# MCU.net
KiCad netlist of a schematic drawn in Altium Designer
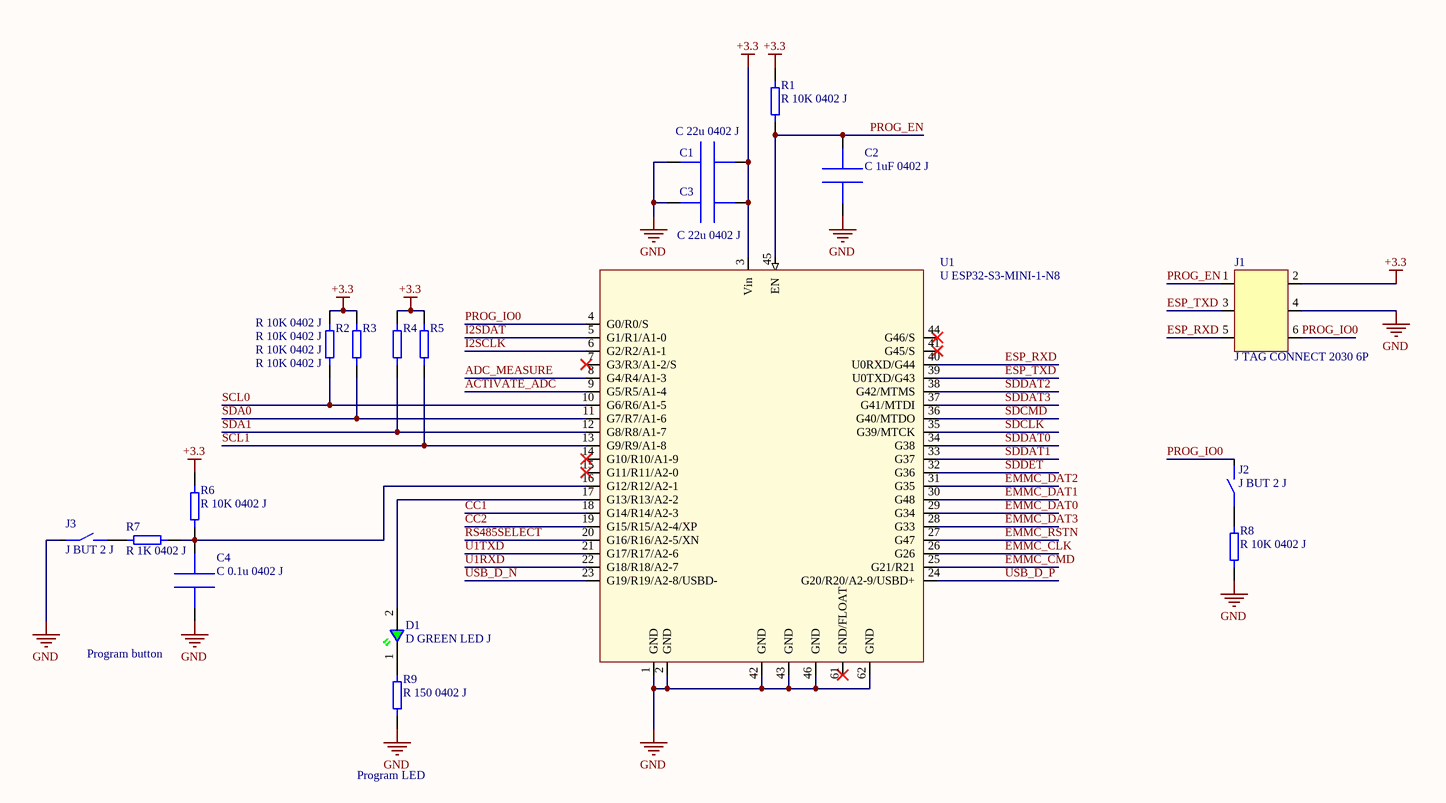
[diagram p0: MCU.SchDoc]

(export (version "E")
  (design (tool "Eeschema 10.0.6"))
  (components
    (comp (ref "C1")
      (value "C 22u 0402 J")
      (footprint "C0402")
      (description "Multi-Layer Ceramic Capacitor 22uF 2.5VDC X6S 20% 0402 Paper T/R GRM155C80E226ME11D")
      (fields
        (field (name "MANUFACTURER") "Murata")
        (field (name "MANUFACTURER PART NUMBER") "GRM155C80E226ME11D")
      )
      (libsource (lib "Schlib1") (part "C 22u 0402 J"))
    )
    (comp (ref "C2")
      (value "C 1uF 0402 J")
      (footprint "C0402")
      (description "Ceramic capacitor SMD 0402 - 1000nF, 10V, +-10%, X5R CL05A105KP5NNNC")
      (fields
        (field (name "MANUFACTURER") "Samsung")
        (field (name "MANUFACTURER PART NUMBER") "CL05A105KP5NNNC")
      )
      (libsource (lib "Schlib1") (part "C 1uF 0402 J"))
    )
    (comp (ref "C3")
      (value "C 22u 0402 J")
      (footprint "C0402")
      (description "Multi-Layer Ceramic Capacitor 22uF 2.5VDC X6S 20% 0402 Paper T/R GRM155C80E226ME11D")
      (fields
        (field (name "MANUFACTURER") "Murata")
        (field (name "MANUFACTURER PART NUMBER") "GRM155C80E226ME11D")
      )
      (libsource (lib "Schlib1") (part "C 22u 0402 J"))
    )
    (comp (ref "C4")
      (value "C 0.1u 0402 J")
      (footprint "C0402")
      (description "Cap Ceramic 0.1uF 50V X7R 10% Pad SMD 0402 125C Low ESR Automotive CL05B104KB54PNC")
      (fields
        (field (name "MANUFACTURER") "Samsung")
        (field (name "MANUFACTURER PART NUMBER") "CL05B104KB54PNC")
      )
      (libsource (lib "Schlib1") (part "C 0.1u 0402 J"))
    )
    (comp (ref "D1")
      (value "D GREEN LED J")
      (footprint "NCD0402C1")
      (description "Green/Yellow-Green 0402 Light Emitting Diodes (LED) ROHS NCD0402C1")
      (fields
        (field (name "MANUFACTURER") "Foshan NationStar Optoelectronics")
        (field (name "MANUFACTURER PART NUMBER") "NCD0402C1")
      )
      (libsource (lib "Schlib1") (part "D GREEN LED J"))
    )
    (comp (ref "J1")
      (value "J TAG CONNECT 2030 6P")
      (footprint "TAG-CONNECT-6")
      (description "Direct programming with TAG CONNECT 2030")
      (libsource (lib "Schlib1") (part "J TAG CONNECT 2030 6P"))
    )
    (comp (ref "J2")
      (value "J BUT 2 J")
      (footprint "ALPSALPINE BUTTON")
      (description "Switch Tactile N.O. SPST Round Button Gull Wing 0.05A 12VDC 1.57N SMD T/R SKRKAEE020")
      (fields
        (field (name "MANUFACTURER") "Alps Electric")
        (field (name "MANUFACTURER PART NUMBER") "SKRKAEE020")
      )
      (libsource (lib "Schlib1") (part "J BUT 2 J"))
    )
    (comp (ref "J3")
      (value "J BUT 2 J")
      (footprint "ALPSALPINE BUTTON")
      (description "Switch Tactile N.O. SPST Round Button Gull Wing 0.05A 12VDC 1.57N SMD T/R SKRKAEE020")
      (fields
        (field (name "MANUFACTURER") "Alps Electric")
        (field (name "MANUFACTURER PART NUMBER") "SKRKAEE020")
      )
      (libsource (lib "Schlib1") (part "J BUT 2 J"))
    )
    (comp (ref "R1")
      (value "R 10K 0402 J")
      (footprint "R0402")
      (description "Res Thick Film 0402 10K Ohm 1% 0.063W(1/16W) ±100ppm/C Pad SMD Automotive T/R AC0402FR-0710KL")
      (fields
        (field (name "MANUFACTURER") "Yageo")
        (field (name "MANUFACTURER PART NUMBER") "AC0402FR-0710KL")
      )
      (libsource (lib "Schlib1") (part "R 10K 0402 J"))
    )
    (comp (ref "R2")
      (value "R 10K 0402 J")
      (footprint "R0402")
      (description "Res Thick Film 0402 10K Ohm 1% 0.063W(1/16W) ±100ppm/C Pad SMD Automotive T/R AC0402FR-0710KL")
      (fields
        (field (name "MANUFACTURER") "Yageo")
        (field (name "MANUFACTURER PART NUMBER") "AC0402FR-0710KL")
      )
      (libsource (lib "Schlib1") (part "R 10K 0402 J"))
    )
    (comp (ref "R3")
      (value "R 10K 0402 J")
      (footprint "R0402")
      (description "Res Thick Film 0402 10K Ohm 1% 0.063W(1/16W) ±100ppm/C Pad SMD Automotive T/R AC0402FR-0710KL")
      (fields
        (field (name "MANUFACTURER") "Yageo")
        (field (name "MANUFACTURER PART NUMBER") "AC0402FR-0710KL")
      )
      (libsource (lib "Schlib1") (part "R 10K 0402 J"))
    )
    (comp (ref "R4")
      (value "R 10K 0402 J")
      (footprint "R0402")
      (description "Res Thick Film 0402 10K Ohm 1% 0.063W(1/16W) ±100ppm/C Pad SMD Automotive T/R AC0402FR-0710KL")
      (fields
        (field (name "MANUFACTURER") "Yageo")
        (field (name "MANUFACTURER PART NUMBER") "AC0402FR-0710KL")
      )
      (libsource (lib "Schlib1") (part "R 10K 0402 J"))
    )
    (comp (ref "R5")
      (value "R 10K 0402 J")
      (footprint "R0402")
      (description "Res Thick Film 0402 10K Ohm 1% 0.063W(1/16W) ±100ppm/C Pad SMD Automotive T/R AC0402FR-0710KL")
      (fields
        (field (name "MANUFACTURER") "Yageo")
        (field (name "MANUFACTURER PART NUMBER") "AC0402FR-0710KL")
      )
      (libsource (lib "Schlib1") (part "R 10K 0402 J"))
    )
    (comp (ref "R6")
      (value "R 10K 0402 J")
      (footprint "R0402")
      (description "Res Thick Film 0402 10K Ohm 1% 0.063W(1/16W) ±100ppm/C Pad SMD Automotive T/R AC0402FR-0710KL")
      (fields
        (field (name "MANUFACTURER") "Yageo")
        (field (name "MANUFACTURER PART NUMBER") "AC0402FR-0710KL")
      )
      (libsource (lib "Schlib1") (part "R 10K 0402 J"))
    )
    (comp (ref "R7")
      (value "R 1K 0402 J")
      (footprint "R0402")
      (description "Res Thick Film 0402 1K Ohm 1% 0.063W(1/16W) ±100ppm/C Pad SMD Automotive T/R")
      (fields
        (field (name "MANUFACTURER") "Yageo")
        (field (name "MANUFACTURER PART NUMBER") "AC0402FR-071KL")
      )
      (libsource (lib "Schlib1") (part "R 1K 0402 J"))
    )
    (comp (ref "R8")
      (value "R 10K 0402 J")
      (footprint "R0402")
      (description "Res Thick Film 0402 10K Ohm 1% 0.063W(1/16W) ±100ppm/C Pad SMD Automotive T/R AC0402FR-0710KL")
      (fields
        (field (name "MANUFACTURER") "Yageo")
        (field (name "MANUFACTURER PART NUMBER") "AC0402FR-0710KL")
      )
      (libsource (lib "Schlib1") (part "R 10K 0402 J"))
    )
    (comp (ref "R9")
      (value "R 150 0402 J")
      (footprint "R0402")
      (fields
        (field (name "MANUFACTURER") "Yageo")
        (field (name "MANUFACTURER PART NUMBER") "RC0402FR-07150RL")
        (field (name "TOLERANCE") "1%")
      )
      (libsource (lib "Schlib1") (part "R 150 0402 J"))
    )
    (comp (ref "U1")
      (value "U ESP32-S3-MINI-1-N8")
      (footprint "ESP-S3-MINI")
      (description "SMD Module, ESP32-S3FN8, 8 mb Sp ESP32-S3-MINI-1-N8")
      (fields
        (field (name "MANUFACTURER") "Espressif Systems")
        (field (name "MANUFACTURER PART NUMBER") "ESP32-S3-MINI-1-N8")
      )
      (libsource (lib "Schlib1") (part "U ESP32-S3-MINI-1-N8"))
    )
  )
  (nets
    (net (code "1") (name "+3.3") (class "Default")
      (node (ref "C1") (pin "1") (pinfunction "1_1") (pintype "passive"))
      (node (ref "C3") (pin "1") (pinfunction "1_1") (pintype "passive"))
      (node (ref "J1") (pin "2") (pintype "passive"))
      (node (ref "R1") (pin "2") (pinfunction "2_2") (pintype "passive"))
      (node (ref "R2") (pin "2") (pinfunction "2_2") (pintype "passive"))
      (node (ref "R3") (pin "2") (pinfunction "2_2") (pintype "passive"))
      (node (ref "R4") (pin "2") (pinfunction "2_2") (pintype "passive"))
      (node (ref "R5") (pin "2") (pinfunction "2_2") (pintype "passive"))
      (node (ref "R6") (pin "2") (pinfunction "2_2") (pintype "passive"))
      (node (ref "U1") (pin "3") (pinfunction "Vin_3") (pintype "power_in"))
    )
    (net (code "2") (name "/ACTIVATE_ADC") (class "Default")
      (node (ref "U1") (pin "9") (pinfunction "G5/R5/A1-4_9") (pintype "bidirectional"))
    )
    (net (code "3") (name "/ADC_MEASURE") (class "Default")
      (node (ref "U1") (pin "8") (pinfunction "G4/R4/A1-3_8") (pintype "bidirectional"))
    )
    (net (code "4") (name "/CC1") (class "Default")
      (node (ref "U1") (pin "18") (pinfunction "G14/R14/A2-3_18") (pintype "bidirectional"))
    )
    (net (code "5") (name "/CC2") (class "Default")
      (node (ref "U1") (pin "19") (pinfunction "G15/R15/A2-4/XP_19") (pintype "bidirectional"))
    )
    (net (code "6") (name "/EMMC_CLK") (class "Default")
      (node (ref "U1") (pin "26") (pinfunction "G26_26") (pintype "bidirectional"))
    )
    (net (code "7") (name "/EMMC_CMD") (class "Default")
      (node (ref "U1") (pin "25") (pinfunction "G21/R21_25") (pintype "bidirectional"))
    )
    (net (code "8") (name "/EMMC_DAT0") (class "Default")
      (node (ref "U1") (pin "29") (pinfunction "G34_29") (pintype "bidirectional"))
    )
    (net (code "9") (name "/EMMC_DAT1") (class "Default")
      (node (ref "U1") (pin "30") (pinfunction "G48_30") (pintype "bidirectional"))
    )
    (net (code "10") (name "/EMMC_DAT2") (class "Default")
      (node (ref "U1") (pin "31") (pinfunction "G35_31") (pintype "bidirectional"))
    )
    (net (code "11") (name "/EMMC_DAT3") (class "Default")
      (node (ref "U1") (pin "28") (pinfunction "G33_28") (pintype "bidirectional"))
    )
    (net (code "12") (name "/EMMC_RSTN") (class "Default")
      (node (ref "U1") (pin "27") (pinfunction "G47_27") (pintype "bidirectional"))
    )
    (net (code "13") (name "/ESP_RXD") (class "Default")
      (node (ref "J1") (pin "5") (pintype "passive"))
      (node (ref "U1") (pin "40") (pinfunction "U0RXD/G44_40") (pintype "bidirectional"))
    )
    (net (code "14") (name "/ESP_TXD") (class "Default")
      (node (ref "J1") (pin "3") (pintype "passive"))
      (node (ref "U1") (pin "39") (pinfunction "U0TXD/G43_39") (pintype "bidirectional"))
    )
    (net (code "15") (name "/I2SCLK") (class "Default")
      (node (ref "U1") (pin "6") (pinfunction "G2/R2/A1-1_6") (pintype "bidirectional"))
    )
    (net (code "16") (name "/I2SDAT") (class "Default")
      (node (ref "U1") (pin "5") (pinfunction "G1/R1/A1-0_5") (pintype "bidirectional"))
    )
    (net (code "17") (name "/PROG_EN") (class "Default")
      (node (ref "C2") (pin "2") (pinfunction "2_2") (pintype "passive"))
      (node (ref "J1") (pin "1") (pintype "passive"))
      (node (ref "R1") (pin "1") (pinfunction "1_1") (pintype "passive"))
      (node (ref "U1") (pin "45") (pinfunction "EN_45") (pintype "input"))
    )
    (net (code "18") (name "/PROG_IO0") (class "Default")
      (node (ref "J1") (pin "6") (pintype "passive"))
      (node (ref "J2") (pin "2") (pinfunction "2_2") (pintype "passive"))
      (node (ref "U1") (pin "4") (pinfunction "G0/R0/S_4") (pintype "bidirectional"))
    )
    (net (code "19") (name "/RS485SELECT") (class "Default")
      (node (ref "U1") (pin "20") (pinfunction "G16/R16/A2-5/XN_20") (pintype "bidirectional"))
    )
    (net (code "20") (name "/SCL0") (class "Default")
      (node (ref "R2") (pin "1") (pinfunction "1_1") (pintype "passive"))
      (node (ref "U1") (pin "10") (pinfunction "G6/R6/A1-5_10") (pintype "bidirectional"))
    )
    (net (code "21") (name "/SCL1") (class "Default")
      (node (ref "R5") (pin "1") (pinfunction "1_1") (pintype "passive"))
      (node (ref "U1") (pin "13") (pinfunction "G9/R9/A1-8_13") (pintype "bidirectional"))
    )
    (net (code "22") (name "/SDA1") (class "Default")
      (node (ref "R4") (pin "1") (pinfunction "1_1") (pintype "passive"))
      (node (ref "U1") (pin "12") (pinfunction "G8/R8/A1-7_12") (pintype "bidirectional"))
    )
    (net (code "23") (name "/SDA~{0}") (class "Default")
      (node (ref "R3") (pin "1") (pinfunction "1_1") (pintype "passive"))
      (node (ref "U1") (pin "11") (pinfunction "G7/R7/A1-6_11") (pintype "bidirectional"))
    )
    (net (code "24") (name "/SDCLK") (class "Default")
      (node (ref "U1") (pin "35") (pinfunction "G39/MTCK_35") (pintype "bidirectional"))
    )
    (net (code "25") (name "/SDCMD") (class "Default")
      (node (ref "U1") (pin "36") (pinfunction "G40/MTDO_36") (pintype "bidirectional"))
    )
    (net (code "26") (name "/SDDAT0") (class "Default")
      (node (ref "U1") (pin "34") (pinfunction "G38_34") (pintype "bidirectional"))
    )
    (net (code "27") (name "/SDDAT1") (class "Default")
      (node (ref "U1") (pin "33") (pinfunction "G37_33") (pintype "bidirectional"))
    )
    (net (code "28") (name "/SDDAT2") (class "Default")
      (node (ref "U1") (pin "38") (pinfunction "G42/MTMS_38") (pintype "bidirectional"))
    )
    (net (code "29") (name "/SDDAT3") (class "Default")
      (node (ref "U1") (pin "37") (pinfunction "G41/MTDI_37") (pintype "bidirectional"))
    )
    (net (code "30") (name "/SDDET") (class "Default")
      (node (ref "U1") (pin "32") (pinfunction "G36_32") (pintype "bidirectional"))
    )
    (net (code "31") (name "/U1RXD") (class "Default")
      (node (ref "U1") (pin "22") (pinfunction "G18/R18/A2-7_22") (pintype "bidirectional"))
    )
    (net (code "32") (name "/U1TXD") (class "Default")
      (node (ref "U1") (pin "21") (pinfunction "G17/R17/A2-6_21") (pintype "bidirectional"))
    )
    (net (code "33") (name "/USB_D_N") (class "Default")
      (node (ref "U1") (pin "23") (pinfunction "G19/R19/A2-8/USBD-_23") (pintype "bidirectional"))
    )
    (net (code "34") (name "/USB_D_P") (class "Default")
      (node (ref "U1") (pin "24") (pinfunction "G20/R20/A2-9/USBD+_24") (pintype "bidirectional"))
    )
    (net (code "35") (name "GND") (class "Default")
      (node (ref "C1") (pin "2") (pinfunction "2_2") (pintype "passive"))
      (node (ref "C2") (pin "1") (pinfunction "1_1") (pintype "passive"))
      (node (ref "C3") (pin "2") (pinfunction "2_2") (pintype "passive"))
      (node (ref "C4") (pin "1") (pinfunction "1_1") (pintype "passive"))
      (node (ref "J1") (pin "4") (pintype "passive"))
      (node (ref "J3") (pin "1") (pinfunction "1_1") (pintype "passive"))
      (node (ref "R8") (pin "1") (pinfunction "1_1") (pintype "passive"))
      (node (ref "R9") (pin "1") (pinfunction "1_1") (pintype "passive"))
      (node (ref "U1") (pin "1") (pinfunction "GND_1") (pintype "power_in"))
      (node (ref "U1") (pin "2") (pinfunction "GND_2") (pintype "power_in"))
      (node (ref "U1") (pin "42") (pinfunction "GND_42") (pintype "power_in"))
      (node (ref "U1") (pin "43") (pinfunction "GND_43") (pintype "power_in"))
      (node (ref "U1") (pin "46") (pinfunction "GND_46") (pintype "power_in"))
      (node (ref "U1") (pin "62") (pinfunction "GND_62") (pintype "power_in"))
    )
    (net (code "36") (name "Net-(D1-Pad1)") (class "Default")
      (node (ref "D1") (pin "1") (pinfunction "1_1") (pintype "passive"))
      (node (ref "R9") (pin "2") (pinfunction "2_2") (pintype "passive"))
    )
    (net (code "37") (name "Net-(J2-Pad1)") (class "Default")
      (node (ref "J2") (pin "1") (pinfunction "1_1") (pintype "passive"))
      (node (ref "R8") (pin "2") (pinfunction "2_2") (pintype "passive"))
    )
    (net (code "38") (name "Net-(J3-Pad2)") (class "Default")
      (node (ref "J3") (pin "2") (pinfunction "2_2") (pintype "passive"))
      (node (ref "R7") (pin "1") (pinfunction "1_1") (pintype "passive"))
    )
    (net (code "39") (name "Net-(U1-G12{slash}R12{slash}A2-1)") (class "Default")
      (node (ref "C4") (pin "2") (pinfunction "2_2") (pintype "passive"))
      (node (ref "R6") (pin "1") (pinfunction "1_1") (pintype "passive"))
      (node (ref "R7") (pin "2") (pinfunction "2_2") (pintype "passive"))
      (node (ref "U1") (pin "16") (pinfunction "G12/R12/A2-1_16") (pintype "bidirectional"))
    )
    (net (code "40") (name "Net-(U1-G13{slash}R13{slash}A2-2)") (class "Default")
      (node (ref "D1") (pin "2") (pinfunction "2_2") (pintype "passive"))
      (node (ref "U1") (pin "17") (pinfunction "G13/R13/A2-2_17") (pintype "bidirectional"))
    )
    (net (code "41") (name "unconnected-(U1-G3{slash}R3{slash}A1-2{slash}S-Pad7)") (class "Default")
      (node (ref "U1") (pin "7") (pinfunction "G3/R3/A1-2/S_7") (pintype "bidirectional+no_connect"))
    )
    (net (code "42") (name "unconnected-(U1-G10{slash}R10{slash}A1-9-Pad14)") (class "Default")
      (node (ref "U1") (pin "14") (pinfunction "G10/R10/A1-9_14") (pintype "bidirectional+no_connect"))
    )
    (net (code "43") (name "unconnected-(U1-G11{slash}R11{slash}A2-0-Pad15)") (class "Default")
      (node (ref "U1") (pin "15") (pinfunction "G11/R11/A2-0_15") (pintype "bidirectional+no_connect"))
    )
    (net (code "44") (name "unconnected-(U1-G45{slash}S-Pad41)") (class "Default")
      (node (ref "U1") (pin "41") (pinfunction "G45/S_41") (pintype "bidirectional+no_connect"))
    )
    (net (code "45") (name "unconnected-(U1-G46{slash}S-Pad44)") (class "Default")
      (node (ref "U1") (pin "44") (pinfunction "G46/S_44") (pintype "bidirectional+no_connect"))
    )
    (net (code "46") (name "unconnected-(U1-GND{slash}FLOAT-Pad61)") (class "Default")
      (node (ref "U1") (pin "61") (pinfunction "GND/FLOAT_61") (pintype "passive+no_connect"))
    )
  )
)
